# prelab2.net
KiCad netlist of a schematic drawn in Altium Designer
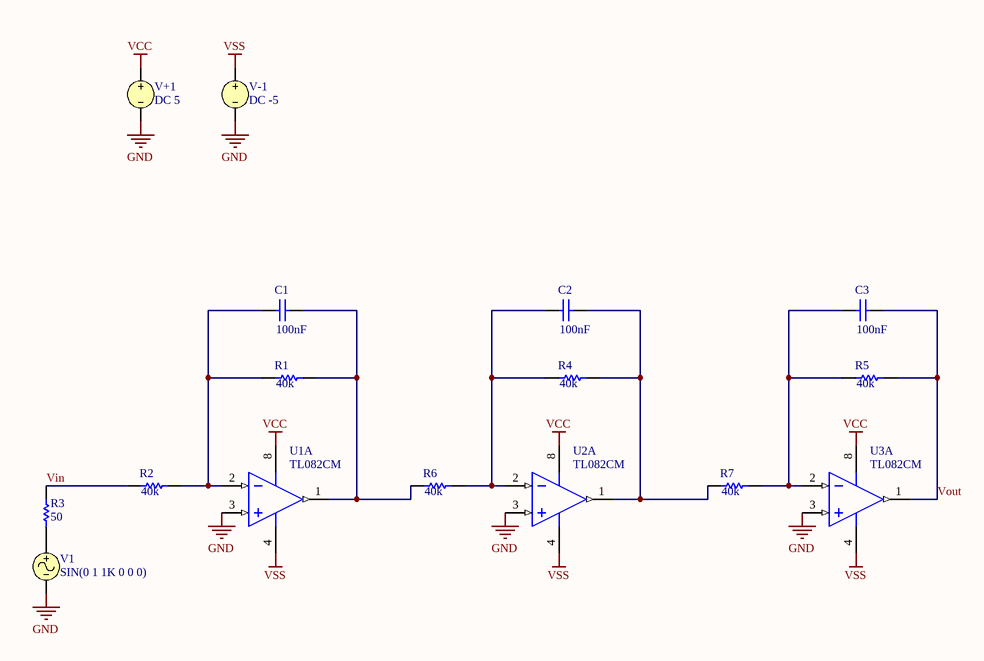
[diagram p0: prelab2.SchDoc]

(export (version "E")
  (design (tool "Eeschema 10.0.6"))
  (components
    (comp (ref "C1")
      (value "100nF")
      (footprint "RAD-0.3")
      (description "Capacitor")
      (fields (field (name "Comment") "Cap") (field (name "PUBLISHER") "Altium Limited"))
      (libsource (lib "Miscellaneous Devices") (part "Cap"))
    )
    (comp (ref "C2")
      (value "100nF")
      (footprint "RAD-0.3")
      (description "Capacitor")
      (fields (field (name "Comment") "Cap") (field (name "PUBLISHER") "Altium Limited"))
      (libsource (lib "Miscellaneous Devices") (part "Cap"))
    )
    (comp (ref "C3")
      (value "100nF")
      (footprint "RAD-0.3")
      (description "Capacitor")
      (fields (field (name "Comment") "Cap") (field (name "PUBLISHER") "Altium Limited"))
      (libsource (lib "Miscellaneous Devices") (part "Cap"))
    )
    (comp (ref "R1")
      (value "40k")
      (footprint "AXIAL-0.3")
      (description "Resistor")
      (fields (field (name "Comment") "Res1") (field (name "PUBLISHER") "Altium Limited"))
      (libsource (lib "Miscellaneous Devices") (part "Res1"))
    )
    (comp (ref "R2")
      (value "40k")
      (footprint "AXIAL-0.3")
      (description "Resistor")
      (fields (field (name "Comment") "Res1") (field (name "PUBLISHER") "Altium Limited"))
      (libsource (lib "Miscellaneous Devices") (part "Res1"))
    )
    (comp (ref "R3")
      (value "50")
      (footprint "AXIAL-0.3")
      (description "Resistor")
      (fields (field (name "Comment") "Res1") (field (name "PUBLISHER") "Altium Limited"))
      (libsource (lib "Miscellaneous Devices") (part "Res1"))
    )
    (comp (ref "R4")
      (value "40k")
      (footprint "AXIAL-0.3")
      (description "Resistor")
      (fields (field (name "Comment") "Res1") (field (name "PUBLISHER") "Altium Limited"))
      (libsource (lib "Miscellaneous Devices") (part "Res1"))
    )
    (comp (ref "R5")
      (value "40k")
      (footprint "AXIAL-0.3")
      (description "Resistor")
      (fields (field (name "Comment") "Res1") (field (name "PUBLISHER") "Altium Limited"))
      (libsource (lib "Miscellaneous Devices") (part "Res1"))
    )
    (comp (ref "R6")
      (value "40k")
      (footprint "AXIAL-0.3")
      (description "Resistor")
      (fields (field (name "Comment") "Res1") (field (name "PUBLISHER") "Altium Limited"))
      (libsource (lib "Miscellaneous Devices") (part "Res1"))
    )
    (comp (ref "R7")
      (value "40k")
      (footprint "AXIAL-0.3")
      (description "Resistor")
      (fields (field (name "Comment") "Res1") (field (name "PUBLISHER") "Altium Limited"))
      (libsource (lib "Miscellaneous Devices") (part "Res1"))
    )
    (comp (ref "U1")
      (value "TL082CM")
      (footprint "M08A_N")
      (description "Wide Bandwidth Dual JFET Input Operational Amplifier")
      (fields
        (field (name "MANUFACTURER") "National Semiconductor")
        (field (name "DIGIKEYPARTNUMBER") "TL082CM-ND")
        (field (name "PUBLISHER") "Altium Limited")
      )
      (libsource (lib "NSC Amplifier") (part "TL082CM"))
    )
    (comp (ref "U2")
      (value "TL082CM")
      (footprint "M08A_N")
      (description "Wide Bandwidth Dual JFET Input Operational Amplifier")
      (fields
        (field (name "MANUFACTURER") "National Semiconductor")
        (field (name "DIGIKEYPARTNUMBER") "TL082CM-ND")
        (field (name "PUBLISHER") "Altium Limited")
      )
      (libsource (lib "NSC Amplifier") (part "TL082CM"))
    )
    (comp (ref "U3")
      (value "TL082CM")
      (footprint "M08A_N")
      (description "Wide Bandwidth Dual JFET Input Operational Amplifier")
      (fields
        (field (name "MANUFACTURER") "National Semiconductor")
        (field (name "DIGIKEYPARTNUMBER") "TL082CM-ND")
        (field (name "PUBLISHER") "Altium Limited")
      )
      (libsource (lib "NSC Amplifier") (part "TL082CM"))
    )
    (comp (ref "V+1")
      (value "DC 5")
      (description "Voltage Source")
      (fields (field (name "PUBLISHER") "Altium Limited"))
      (libsource (lib "Simulation Sources") (part "VSRC"))
    )
    (comp (ref "V-1")
      (value "DC -5")
      (description "Voltage Source")
      (fields (field (name "PUBLISHER") "Altium Limited"))
      (libsource (lib "Simulation Sources") (part "VSRC"))
    )
    (comp (ref "V1")
      (value "SIN(0 1 1K 0 0 0)")
      (description "Sinusoidal Voltage Source")
      (fields (field (name "PUBLISHER") "Altium Limited"))
      (libsource (lib "Simulation Sources") (part "VSIN"))
    )
  )
  (nets
    (net (code "1") (name "/Vin") (class "Default")
      (node (ref "R2") (pin "1") (pinfunction "1_1") (pintype "passive"))
      (node (ref "R3") (pin "2") (pinfunction "2_2") (pintype "passive"))
    )
    (net (code "2") (name "/Vout") (class "Default")
      (node (ref "C3") (pin "2") (pinfunction "2_2") (pintype "passive"))
      (node (ref "R5") (pin "2") (pinfunction "2_2") (pintype "passive"))
      (node (ref "U3") (pin "1") (pinfunction "OUTA_1") (pintype "output"))
    )
    (net (code "3") (name "GND") (class "Default")
      (node (ref "U1") (pin "3") (pinfunction "INA+_3") (pintype "input"))
      (node (ref "U2") (pin "3") (pinfunction "INA+_3") (pintype "input"))
      (node (ref "U3") (pin "3") (pinfunction "INA+_3") (pintype "input"))
      (node (ref "V+1") (pin "2") (pinfunction "2_2") (pintype "passive"))
      (node (ref "V-1") (pin "2") (pinfunction "2_2") (pintype "passive"))
      (node (ref "V1") (pin "2") (pinfunction "2_2") (pintype "passive"))
    )
    (net (code "4") (name "Net-(R3-Pad1)") (class "Default")
      (node (ref "R3") (pin "1") (pinfunction "1_1") (pintype "passive"))
      (node (ref "V1") (pin "1") (pinfunction "1_1") (pintype "passive"))
    )
    (net (code "5") (name "Net-(U1A-INA-)") (class "Default")
      (node (ref "C1") (pin "1") (pinfunction "1_1") (pintype "passive"))
      (node (ref "R1") (pin "1") (pinfunction "1_1") (pintype "passive"))
      (node (ref "R2") (pin "2") (pinfunction "2_2") (pintype "passive"))
      (node (ref "U1") (pin "2") (pinfunction "INA-_2") (pintype "input"))
    )
    (net (code "6") (name "Net-(U1A-OUTA)") (class "Default")
      (node (ref "C1") (pin "2") (pinfunction "2_2") (pintype "passive"))
      (node (ref "R1") (pin "2") (pinfunction "2_2") (pintype "passive"))
      (node (ref "R6") (pin "1") (pinfunction "1_1") (pintype "passive"))
      (node (ref "U1") (pin "1") (pinfunction "OUTA_1") (pintype "output"))
    )
    (net (code "7") (name "Net-(U2A-INA-)") (class "Default")
      (node (ref "C2") (pin "1") (pinfunction "1_1") (pintype "passive"))
      (node (ref "R4") (pin "1") (pinfunction "1_1") (pintype "passive"))
      (node (ref "R6") (pin "2") (pinfunction "2_2") (pintype "passive"))
      (node (ref "U2") (pin "2") (pinfunction "INA-_2") (pintype "input"))
    )
    (net (code "8") (name "Net-(U2A-OUTA)") (class "Default")
      (node (ref "C2") (pin "2") (pinfunction "2_2") (pintype "passive"))
      (node (ref "R4") (pin "2") (pinfunction "2_2") (pintype "passive"))
      (node (ref "R7") (pin "1") (pinfunction "1_1") (pintype "passive"))
      (node (ref "U2") (pin "1") (pinfunction "OUTA_1") (pintype "output"))
    )
    (net (code "9") (name "Net-(U3A-INA-)") (class "Default")
      (node (ref "C3") (pin "1") (pinfunction "1_1") (pintype "passive"))
      (node (ref "R5") (pin "1") (pinfunction "1_1") (pintype "passive"))
      (node (ref "R7") (pin "2") (pinfunction "2_2") (pintype "passive"))
      (node (ref "U3") (pin "2") (pinfunction "INA-_2") (pintype "input"))
    )
    (net (code "10") (name "VCC") (class "Default")
      (node (ref "U1") (pin "8") (pinfunction "V+_8") (pintype "power_in"))
      (node (ref "U2") (pin "8") (pinfunction "V+_8") (pintype "power_in"))
      (node (ref "U3") (pin "8") (pinfunction "V+_8") (pintype "power_in"))
      (node (ref "V+1") (pin "1") (pinfunction "1_1") (pintype "passive"))
    )
    (net (code "11") (name "VSS") (class "Default")
      (node (ref "U1") (pin "4") (pinfunction "V-_4") (pintype "power_in"))
      (node (ref "U2") (pin "4") (pinfunction "V-_4") (pintype "power_in"))
      (node (ref "U3") (pin "4") (pinfunction "V-_4") (pintype "power_in"))
      (node (ref "V-1") (pin "1") (pinfunction "1_1") (pintype "passive"))
    )
  )
)
